# LED_array.net
KiCad netlist of a schematic drawn in Altium Designer
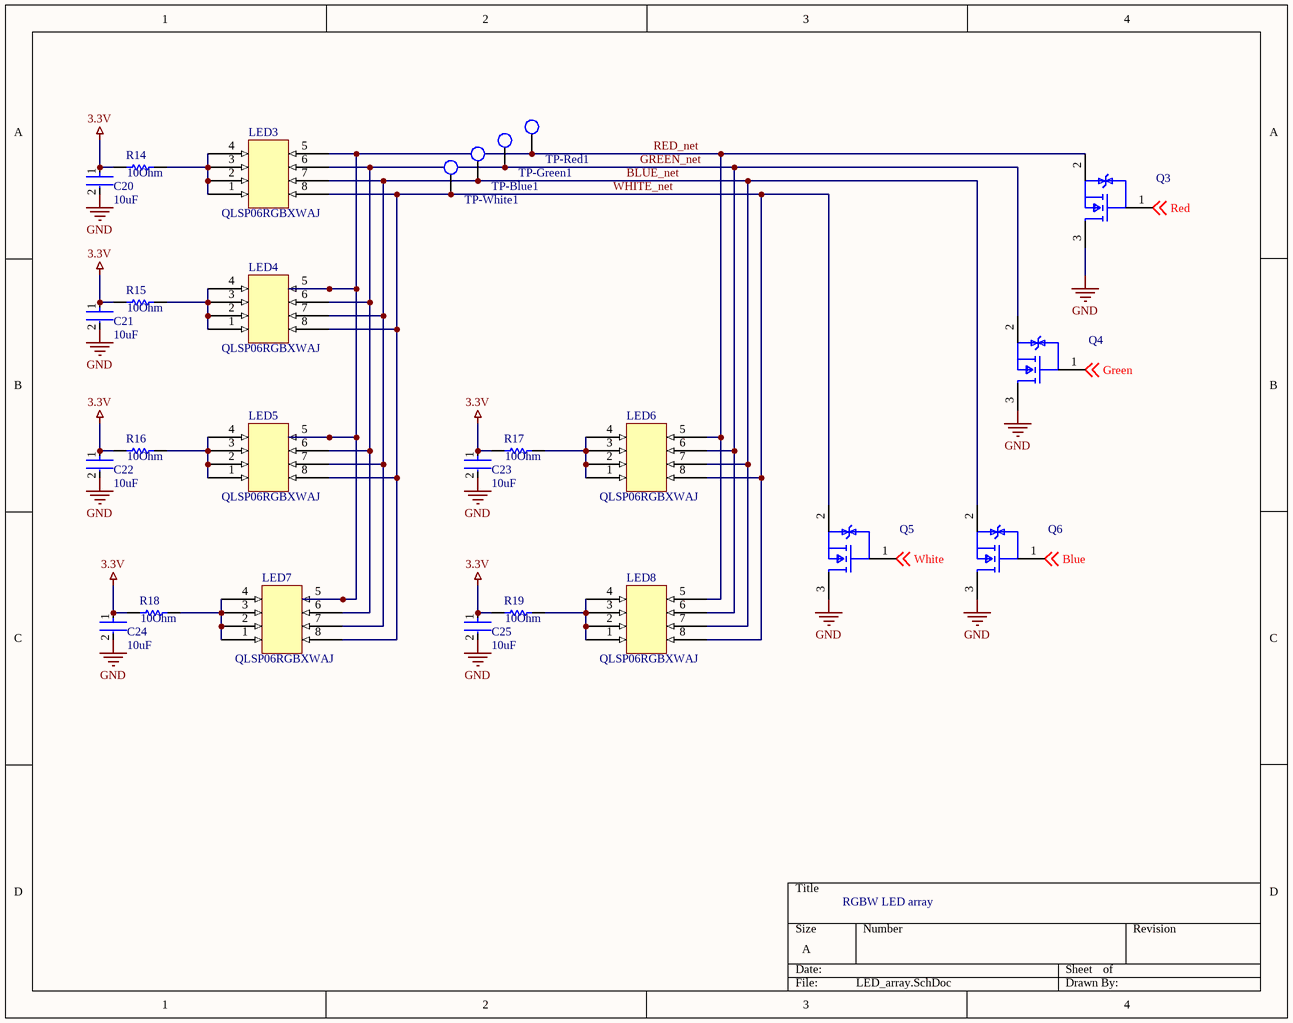
[diagram p0: LED_array.SchDoc]

(export (version "E")
  (design (tool "Eeschema 10.0.6"))
  (components
    (comp (ref "C20")
      (value "10uF")
      (footprint "FP-C0805C-DG-MFG")
      (description "CAP CER 10UF 10V X5R 0805")
      (fields (field (name "TOLERANCE") "10%") (field (name "MANUFACTURER PART NUMBER") "C0805C106K8PACTU"))
      (libsource (lib "Altium Content Vault") (part "11868f565c42a9108669ba33697ecf6"))
    )
    (comp (ref "C21")
      (value "10uF")
      (footprint "FP-C0805C-DG-MFG")
      (description "CAP CER 10UF 10V X5R 0805")
      (fields (field (name "TOLERANCE") "10%") (field (name "MANUFACTURER PART NUMBER") "C0805C106K8PACTU"))
      (libsource (lib "Altium Content Vault") (part "11868f565c42a9108669ba33697ecf6"))
    )
    (comp (ref "C22")
      (value "10uF")
      (footprint "FP-C0805C-DG-MFG")
      (description "CAP CER 10UF 10V X5R 0805")
      (fields (field (name "TOLERANCE") "10%") (field (name "MANUFACTURER PART NUMBER") "C0805C106K8PACTU"))
      (libsource (lib "Altium Content Vault") (part "11868f565c42a9108669ba33697ecf6"))
    )
    (comp (ref "C23")
      (value "10uF")
      (footprint "FP-C0805C-DG-MFG")
      (description "CAP CER 10UF 10V X5R 0805")
      (fields (field (name "TOLERANCE") "10%") (field (name "MANUFACTURER PART NUMBER") "C0805C106K8PACTU"))
      (libsource (lib "Altium Content Vault") (part "11868f565c42a9108669ba33697ecf6"))
    )
    (comp (ref "C24")
      (value "10uF")
      (footprint "FP-C0805C-DG-MFG")
      (description "CAP CER 10UF 10V X5R 0805")
      (fields (field (name "TOLERANCE") "10%") (field (name "MANUFACTURER PART NUMBER") "C0805C106K8PACTU"))
      (libsource (lib "Altium Content Vault") (part "11868f565c42a9108669ba33697ecf6"))
    )
    (comp (ref "C25")
      (value "10uF")
      (footprint "FP-C0805C-DG-MFG")
      (description "CAP CER 10UF 10V X5R 0805")
      (fields (field (name "TOLERANCE") "10%") (field (name "MANUFACTURER PART NUMBER") "C0805C106K8PACTU"))
      (libsource (lib "Altium Content Vault") (part "11868f565c42a9108669ba33697ecf6"))
    )
    (comp (ref "LED3")
      (value "QLSP06RGBXWAJ")
      (footprint "LED:QLSP06RGBXWAJ")
      (libsource (lib "LED") (part "Component_1"))
    )
    (comp (ref "LED4")
      (value "QLSP06RGBXWAJ")
      (footprint "LED:QLSP06RGBXWAJ")
      (libsource (lib "LED") (part "Component_1"))
    )
    (comp (ref "LED5")
      (value "QLSP06RGBXWAJ")
      (footprint "LED:QLSP06RGBXWAJ")
      (libsource (lib "LED") (part "Component_1"))
    )
    (comp (ref "LED6")
      (value "QLSP06RGBXWAJ")
      (footprint "LED:QLSP06RGBXWAJ")
      (libsource (lib "LED") (part "Component_1"))
    )
    (comp (ref "LED7")
      (value "QLSP06RGBXWAJ")
      (footprint "LED:QLSP06RGBXWAJ")
      (libsource (lib "LED") (part "Component_1"))
    )
    (comp (ref "LED8")
      (value "QLSP06RGBXWAJ")
      (footprint "LED:QLSP06RGBXWAJ")
      (libsource (lib "LED") (part "Component_1"))
    )
    (comp (ref "Q3")
      (value "SSM3K329R,LF")
      (footprint "FP-2-3Z1A-MFG")
      (description "MOSFET N CH 30V 3.5A 2-3Z1A")
      (libsource (lib "Altium Content Vault") (part "a1640d25ff429ac9f2c6fc6aeb7bb9e"))
    )
    (comp (ref "Q4")
      (value "SSM3K329R,LF")
      (footprint "FP-2-3Z1A-MFG")
      (description "MOSFET N CH 30V 3.5A 2-3Z1A")
      (libsource (lib "Altium Content Vault") (part "a1640d25ff429ac9f2c6fc6aeb7bb9e"))
    )
    (comp (ref "Q5")
      (value "SSM3K329R,LF")
      (footprint "FP-2-3Z1A-MFG")
      (description "MOSFET N CH 30V 3.5A 2-3Z1A")
      (libsource (lib "Altium Content Vault") (part "a1640d25ff429ac9f2c6fc6aeb7bb9e"))
    )
    (comp (ref "Q6")
      (value "SSM3K329R,LF")
      (footprint "FP-2-3Z1A-MFG")
      (description "MOSFET N CH 30V 3.5A 2-3Z1A")
      (libsource (lib "Altium Content Vault") (part "a1640d25ff429ac9f2c6fc6aeb7bb9e"))
    )
    (comp (ref "R14")
      (value "10Ohm")
      (footprint "RESC2013X50X40ML20T20")
      (fields (field (name "MANUFACTURER") "Susumu") (field (name "PART NUMBER") "RL1220S-100-F"))
      (libsource (lib "Altium Content Vault") (part "RES"))
    )
    (comp (ref "R15")
      (value "10Ohm")
      (footprint "RESC2013X50X40ML20T20")
      (fields (field (name "MANUFACTURER") "Susumu") (field (name "PART NUMBER") "RL1220S-100-F"))
      (libsource (lib "Altium Content Vault") (part "RES"))
    )
    (comp (ref "R16")
      (value "10Ohm")
      (footprint "RESC2013X50X40ML20T20")
      (fields (field (name "MANUFACTURER") "Susumu") (field (name "PART NUMBER") "RL1220S-100-F"))
      (libsource (lib "Altium Content Vault") (part "RES"))
    )
    (comp (ref "R17")
      (value "10Ohm")
      (footprint "RESC2013X50X40ML20T20")
      (fields (field (name "MANUFACTURER") "Susumu") (field (name "PART NUMBER") "RL1220S-100-F"))
      (libsource (lib "Altium Content Vault") (part "RES"))
    )
    (comp (ref "R18")
      (value "10Ohm")
      (footprint "RESC2013X50X40ML20T20")
      (fields (field (name "MANUFACTURER") "Susumu") (field (name "PART NUMBER") "RL1220S-100-F"))
      (libsource (lib "Altium Content Vault") (part "RES"))
    )
    (comp (ref "R19")
      (value "10Ohm")
      (footprint "RESC2013X50X40ML20T20")
      (fields (field (name "MANUFACTURER") "Susumu") (field (name "PART NUMBER") "RL1220S-100-F"))
      (libsource (lib "Altium Content Vault") (part "RES"))
    )
    (comp (ref "TP-Blue1")
      (value "TP_1206")
      (footprint "TP-SMC-1206")
      (description "Test Point SMD 1206")
      (fields
        (field (name "MANUFACTURER") "TE Connectivity (Tyco Electronics)")
        (field (name "MANUFACTURER PART NUMBER") "1625854-1")
      )
      (libsource (lib "ECE453-F22-Power") (part "TP_1206"))
    )
    (comp (ref "TP-Green1")
      (value "TP_1206")
      (footprint "TP-SMC-1206")
      (description "Test Point SMD 1206")
      (fields
        (field (name "MANUFACTURER") "TE Connectivity (Tyco Electronics)")
        (field (name "MANUFACTURER PART NUMBER") "1625854-1")
      )
      (libsource (lib "ECE453-F22-Power") (part "TP_1206"))
    )
    (comp (ref "TP-Red1")
      (value "TP_1206")
      (footprint "TP-SMC-1206")
      (description "Test Point SMD 1206")
      (fields
        (field (name "MANUFACTURER") "TE Connectivity (Tyco Electronics)")
        (field (name "MANUFACTURER PART NUMBER") "1625854-1")
      )
      (libsource (lib "ECE453-F22-Power") (part "TP_1206"))
    )
    (comp (ref "TP-White1")
      (value "TP_1206")
      (footprint "TP-SMC-1206")
      (description "Test Point SMD 1206")
      (fields
        (field (name "MANUFACTURER") "TE Connectivity (Tyco Electronics)")
        (field (name "MANUFACTURER PART NUMBER") "1625854-1")
      )
      (libsource (lib "ECE453-F22-Power") (part "TP_1206"))
    )
  )
  (nets
    (net (code "1") (name "/BLUE_net") (class "Default")
      (node (ref "LED3") (pin "7") (pintype "input"))
      (node (ref "LED4") (pin "7") (pintype "input"))
      (node (ref "LED5") (pin "7") (pintype "input"))
      (node (ref "LED6") (pin "7") (pintype "input"))
      (node (ref "LED7") (pin "7") (pintype "input"))
      (node (ref "LED8") (pin "7") (pintype "input"))
      (node (ref "Q6") (pin "2") (pinfunction "SOURCE_2") (pintype "passive"))
      (node (ref "TP-Blue1") (pin "1") (pintype "passive"))
    )
    (net (code "2") (name "/GREEN_net") (class "Default")
      (node (ref "LED3") (pin "6") (pintype "input"))
      (node (ref "LED4") (pin "6") (pintype "input"))
      (node (ref "LED5") (pin "6") (pintype "input"))
      (node (ref "LED6") (pin "6") (pintype "input"))
      (node (ref "LED7") (pin "6") (pintype "input"))
      (node (ref "LED8") (pin "6") (pintype "input"))
      (node (ref "Q4") (pin "2") (pinfunction "SOURCE_2") (pintype "passive"))
      (node (ref "TP-Green1") (pin "1") (pintype "passive"))
    )
    (net (code "3") (name "/RED_net") (class "Default")
      (node (ref "LED3") (pin "5") (pintype "input"))
      (node (ref "LED4") (pin "5") (pintype "input"))
      (node (ref "LED5") (pin "5") (pintype "input"))
      (node (ref "LED6") (pin "5") (pintype "input"))
      (node (ref "LED7") (pin "5") (pintype "input"))
      (node (ref "LED8") (pin "5") (pintype "input"))
      (node (ref "Q3") (pin "2") (pinfunction "SOURCE_2") (pintype "passive"))
      (node (ref "TP-Red1") (pin "1") (pintype "passive"))
    )
    (net (code "4") (name "/WHITE_net") (class "Default")
      (node (ref "LED3") (pin "8") (pintype "input"))
      (node (ref "LED4") (pin "8") (pintype "input"))
      (node (ref "LED5") (pin "8") (pintype "input"))
      (node (ref "LED6") (pin "8") (pintype "input"))
      (node (ref "LED7") (pin "8") (pintype "input"))
      (node (ref "LED8") (pin "8") (pintype "input"))
      (node (ref "Q5") (pin "2") (pinfunction "SOURCE_2") (pintype "passive"))
      (node (ref "TP-White1") (pin "1") (pintype "passive"))
    )
    (net (code "5") (name "3.3V") (class "Default")
      (node (ref "C20") (pin "1") (pinfunction "1_1") (pintype "passive"))
      (node (ref "C21") (pin "1") (pinfunction "1_1") (pintype "passive"))
      (node (ref "C22") (pin "1") (pinfunction "1_1") (pintype "passive"))
      (node (ref "C23") (pin "1") (pinfunction "1_1") (pintype "passive"))
      (node (ref "C24") (pin "1") (pinfunction "1_1") (pintype "passive"))
      (node (ref "C25") (pin "1") (pinfunction "1_1") (pintype "passive"))
      (node (ref "R14") (pin "1") (pinfunction "1_1") (pintype "passive"))
      (node (ref "R15") (pin "1") (pinfunction "1_1") (pintype "passive"))
      (node (ref "R16") (pin "1") (pinfunction "1_1") (pintype "passive"))
      (node (ref "R17") (pin "1") (pinfunction "1_1") (pintype "passive"))
      (node (ref "R18") (pin "1") (pinfunction "1_1") (pintype "passive"))
      (node (ref "R19") (pin "1") (pinfunction "1_1") (pintype "passive"))
    )
    (net (code "6") (name "Blue") (class "Default")
      (node (ref "Q6") (pin "1") (pinfunction "GATE_1") (pintype "passive"))
    )
    (net (code "7") (name "GND") (class "Default")
      (node (ref "C20") (pin "2") (pinfunction "2_2") (pintype "passive"))
      (node (ref "C21") (pin "2") (pinfunction "2_2") (pintype "passive"))
      (node (ref "C22") (pin "2") (pinfunction "2_2") (pintype "passive"))
      (node (ref "C23") (pin "2") (pinfunction "2_2") (pintype "passive"))
      (node (ref "C24") (pin "2") (pinfunction "2_2") (pintype "passive"))
      (node (ref "C25") (pin "2") (pinfunction "2_2") (pintype "passive"))
      (node (ref "Q3") (pin "3") (pinfunction "DRAIN_3") (pintype "passive"))
      (node (ref "Q4") (pin "3") (pinfunction "DRAIN_3") (pintype "passive"))
      (node (ref "Q5") (pin "3") (pinfunction "DRAIN_3") (pintype "passive"))
      (node (ref "Q6") (pin "3") (pinfunction "DRAIN_3") (pintype "passive"))
    )
    (net (code "8") (name "Green") (class "Default")
      (node (ref "Q4") (pin "1") (pinfunction "GATE_1") (pintype "passive"))
    )
    (net (code "9") (name "Net-(LED3-Pad1)") (class "Default")
      (node (ref "LED3") (pin "1") (pintype "input"))
      (node (ref "LED3") (pin "2") (pintype "input"))
      (node (ref "LED3") (pin "3") (pintype "input"))
      (node (ref "LED3") (pin "4") (pintype "input"))
      (node (ref "R14") (pin "2") (pinfunction "2_2") (pintype "passive"))
    )
    (net (code "10") (name "Net-(LED4-Pad1)") (class "Default")
      (node (ref "LED4") (pin "1") (pintype "input"))
      (node (ref "LED4") (pin "2") (pintype "input"))
      (node (ref "LED4") (pin "3") (pintype "input"))
      (node (ref "LED4") (pin "4") (pintype "input"))
      (node (ref "R15") (pin "2") (pinfunction "2_2") (pintype "passive"))
    )
    (net (code "11") (name "Net-(LED5-Pad1)") (class "Default")
      (node (ref "LED5") (pin "1") (pintype "input"))
      (node (ref "LED5") (pin "2") (pintype "input"))
      (node (ref "LED5") (pin "3") (pintype "input"))
      (node (ref "LED5") (pin "4") (pintype "input"))
      (node (ref "R16") (pin "2") (pinfunction "2_2") (pintype "passive"))
    )
    (net (code "12") (name "Net-(LED6-Pad1)") (class "Default")
      (node (ref "LED6") (pin "1") (pintype "input"))
      (node (ref "LED6") (pin "2") (pintype "input"))
      (node (ref "LED6") (pin "3") (pintype "input"))
      (node (ref "LED6") (pin "4") (pintype "input"))
      (node (ref "R17") (pin "2") (pinfunction "2_2") (pintype "passive"))
    )
    (net (code "13") (name "Net-(LED7-Pad1)") (class "Default")
      (node (ref "LED7") (pin "1") (pintype "input"))
      (node (ref "LED7") (pin "2") (pintype "input"))
      (node (ref "LED7") (pin "3") (pintype "input"))
      (node (ref "LED7") (pin "4") (pintype "input"))
      (node (ref "R18") (pin "2") (pinfunction "2_2") (pintype "passive"))
    )
    (net (code "14") (name "Net-(LED8-Pad1)") (class "Default")
      (node (ref "LED8") (pin "1") (pintype "input"))
      (node (ref "LED8") (pin "2") (pintype "input"))
      (node (ref "LED8") (pin "3") (pintype "input"))
      (node (ref "LED8") (pin "4") (pintype "input"))
      (node (ref "R19") (pin "2") (pinfunction "2_2") (pintype "passive"))
    )
    (net (code "15") (name "Red") (class "Default")
      (node (ref "Q3") (pin "1") (pinfunction "GATE_1") (pintype "passive"))
    )
    (net (code "16") (name "White") (class "Default")
      (node (ref "Q5") (pin "1") (pinfunction "GATE_1") (pintype "passive"))
    )
  )
)
